# LEDRGB.net
KiCad netlist of a schematic drawn in Altium Designer
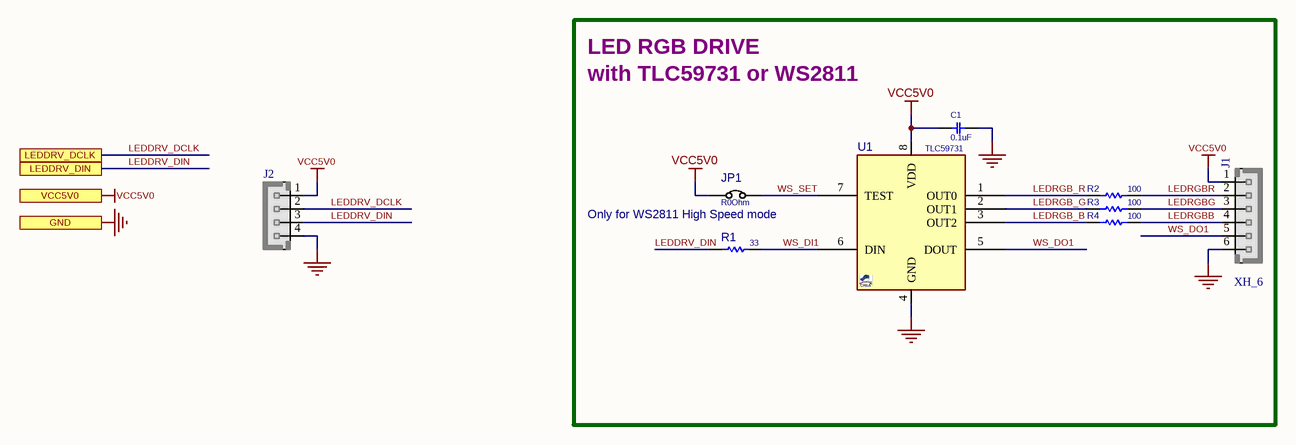
[diagram p0: LEDRGB.SchDoc]

(export (version "E")
  (design (tool "Eeschema 10.0.6"))
  (components
    (comp (ref "C1")
      (value "0.1uF")
      (footprint "C0402")
      (description "CAP, MLCC")
      (fields (field (name "MANF_P#") "GRM155R61E104") (field (name "MANF") "Murata"))
      (libsource (lib "7seg_ShiftRegister") (part "CAP_SMD_MLCC_1"))
    )
    (comp (ref "J1")
      (value "XH_6")
      (footprint "XH_6")
      (description "JST-XH pitch: 2.5mm")
      (fields (field (name "MANF_P#") "JST-S6B-XHA") (field (name "MANF") "JST"))
      (libsource (lib "conn_wire2board") (part "XH_6"))
    )
    (comp (ref "J2")
      (value "HHDR_4")
      (footprint "XH_4")
      (description "JST-XH pitch: 2.5mm")
      (libsource (lib "conn_wire2board") (part "XH_4"))
    )
    (comp (ref "JP1")
      (value "R0Ohm")
      (footprint "JP_60X100")
      (description "JUMPER, HEADER 2PIN")
      (libsource (lib "test-tp_jumper") (part "JUMPER_HDR_2P"))
    )
    (comp (ref "R1")
      (value "33")
      (footprint "R0402")
      (description "RESISTOR, SMD")
      (libsource (lib "7seg_ShiftRegister") (part "RES_SMD_1"))
    )
    (comp (ref "R2")
      (value "100")
      (footprint "R0402")
      (description "RESISTOR, SMD")
      (libsource (lib "7seg_ShiftRegister") (part "RES_SMD_1"))
    )
    (comp (ref "R3")
      (value "100")
      (footprint "R0402")
      (description "RESISTOR, SMD")
      (libsource (lib "7seg_ShiftRegister") (part "RES_SMD_1"))
    )
    (comp (ref "R4")
      (value "100")
      (footprint "R0402")
      (description "RESISTOR, SMD")
      (libsource (lib "7seg_ShiftRegister") (part "RES_SMD_1"))
    )
    (comp (ref "U1")
      (value "TLC59731")
      (footprint "SO_8A")
      (description "Signal line 256 Gray level 3-ch Constant current LED drive")
      (fields (field (name "MANF") "Texas Instruments") (field (name "MANF_P#") "TLC59731D"))
      (libsource (lib "shift_register") (part "TLC59731_SOP8"))
    )
  )
  (nets
    (net (code "1") (name "/LEDDRV_DCLK") (class "Default")
      (node (ref "J2") (pin "2") (pinfunction "2_2") (pintype "passive"))
    )
    (net (code "2") (name "/LEDDRV_DIN") (class "Default")
      (node (ref "J2") (pin "3") (pinfunction "3_3") (pintype "passive"))
      (node (ref "R1") (pin "1") (pinfunction "1_1") (pintype "passive"))
    )
    (net (code "3") (name "/LEDRGBB") (class "Default")
      (node (ref "J1") (pin "4") (pinfunction "4_4") (pintype "passive"))
      (node (ref "R4") (pin "2") (pinfunction "2_2") (pintype "passive"))
    )
    (net (code "4") (name "/LEDRGBG") (class "Default")
      (node (ref "J1") (pin "3") (pinfunction "3_3") (pintype "passive"))
      (node (ref "R3") (pin "2") (pinfunction "2_2") (pintype "passive"))
    )
    (net (code "5") (name "/LEDRGBR") (class "Default")
      (node (ref "J1") (pin "2") (pinfunction "2_2") (pintype "passive"))
      (node (ref "R2") (pin "2") (pinfunction "2_2") (pintype "passive"))
    )
    (net (code "6") (name "/LEDRGB_B") (class "Default")
      (node (ref "R4") (pin "1") (pinfunction "1_1") (pintype "passive"))
      (node (ref "U1") (pin "3") (pinfunction "OUT2_3") (pintype "passive"))
    )
    (net (code "7") (name "/LEDRGB_G") (class "Default")
      (node (ref "R3") (pin "1") (pinfunction "1_1") (pintype "passive"))
      (node (ref "U1") (pin "2") (pinfunction "OUT1_2") (pintype "passive"))
    )
    (net (code "8") (name "/LEDRGB_R") (class "Default")
      (node (ref "R2") (pin "1") (pinfunction "1_1") (pintype "passive"))
      (node (ref "U1") (pin "1") (pinfunction "OUT0_1") (pintype "passive"))
    )
    (net (code "9") (name "/WS_DI1") (class "Default")
      (node (ref "R1") (pin "2") (pinfunction "2_2") (pintype "passive"))
      (node (ref "U1") (pin "6") (pinfunction "DIN_6") (pintype "passive"))
    )
    (net (code "10") (name "/WS_DO1") (class "Default")
      (node (ref "J1") (pin "5") (pinfunction "5_5") (pintype "passive"))
      (node (ref "U1") (pin "5") (pinfunction "DOUT_5") (pintype "passive"))
    )
    (net (code "11") (name "/WS_SET") (class "Default")
      (node (ref "JP1") (pin "2") (pinfunction "2_2") (pintype "passive"))
      (node (ref "U1") (pin "7") (pinfunction "TEST_7") (pintype "passive"))
    )
    (net (code "12") (name "GND") (class "Default")
      (node (ref "C1") (pin "1") (pinfunction "1_1") (pintype "passive"))
      (node (ref "J1") (pin "6") (pinfunction "6_6") (pintype "passive"))
      (node (ref "J2") (pin "4") (pinfunction "4_4") (pintype "passive"))
      (node (ref "U1") (pin "4") (pinfunction "GND_4") (pintype "passive"))
    )
    (net (code "13") (name "VCC5V0") (class "Default")
      (node (ref "C1") (pin "2") (pinfunction "2_2") (pintype "passive"))
      (node (ref "J1") (pin "1") (pinfunction "1_1") (pintype "passive"))
      (node (ref "J2") (pin "1") (pinfunction "1_1") (pintype "passive"))
      (node (ref "JP1") (pin "1") (pinfunction "1_1") (pintype "passive"))
      (node (ref "U1") (pin "8") (pinfunction "VDD_8") (pintype "passive"))
    )
  )
)
